# NewBoard.net
KiCad netlist of a schematic drawn in EAGLE
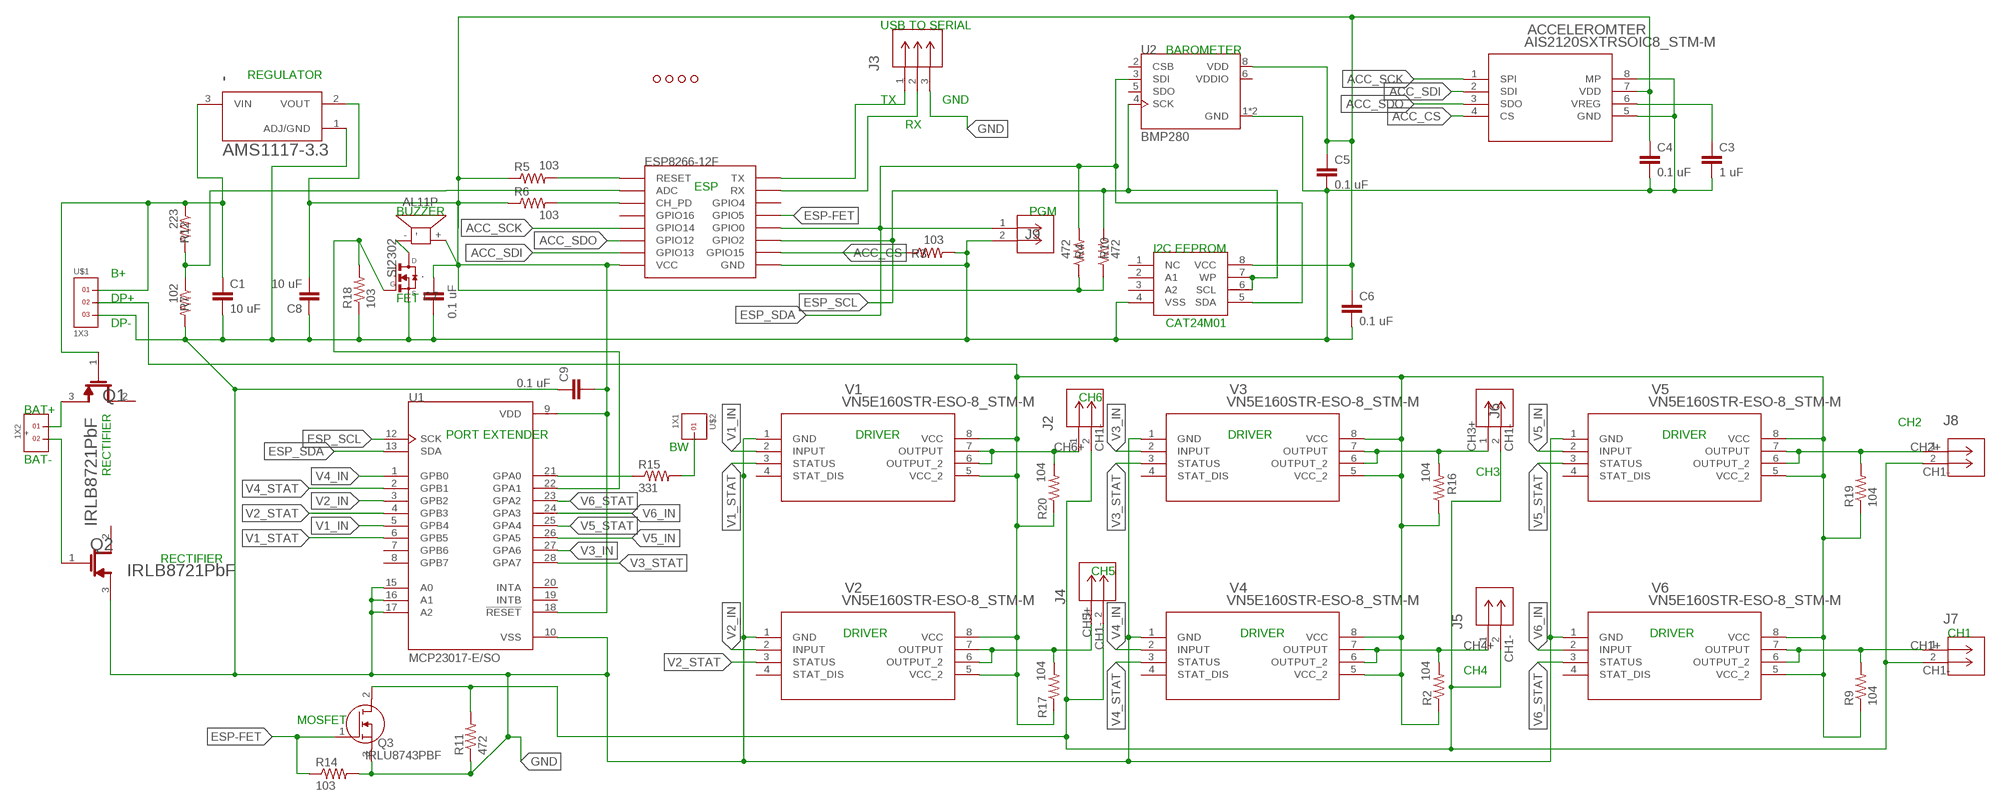
[diagram p0: schematic, sheet 1]

(export (version "E")
  (design (tool "Eeschema 10.0.6"))
  (components
    (comp (ref "'")
      (value "AMS1117-3.3")
      (footprint "eagle-import:SOT229P700X180-4N")
      (fields (field (name "MF") "Advanced Monolithic Systems"))
      (libsource (lib "eagle-import") (part "AMS1117-3.3"))
    )
    (comp (ref "+")
      (value "1X2")
      (footprint "eagle-import:1X2")
      (libsource (lib "eagle-import") (part "1X2"))
    )
    (comp (ref ",")
      (value "AL11P")
      (footprint "eagle-import:AL11P")
      (libsource (lib "eagle-import") (part "AL11P"))
    )
    (comp (ref ".")
      (value "SI2302")
      (footprint "eagle-import:SOT23")
      (fields (field (name "MF") "Vishay Siliconix"))
      (libsource (lib "eagle-import") (part "SI2302"))
    )
    (comp (ref "ACCELEROMTER")
      (value "AIS2120SXTRSOIC8_STM-M")
      (footprint "eagle-import:SOIC8_STM-M")
      (fields
        (field (name "MANUFACTURER_PART_NUMBER") "AIS2120SXTR")
        (field (name "COPYRIGHT") "Copyright (C) 2022 Ultra Librarian. All rights reserved.")
      )
      (libsource (lib "eagle-import") (part "AIS2120SXTRSOIC8_STM-M"))
    )
    (comp (ref "C1")
      (value "10 uF")
      (footprint "eagle-import:C1206")
      (libsource (lib "eagle-import") (part "C-EUC1206"))
    )
    (comp (ref "C3")
      (value "1 uF")
      (footprint "eagle-import:C1206")
      (libsource (lib "eagle-import") (part "C-EUC1206"))
    )
    (comp (ref "C4")
      (value "0.1 uF")
      (footprint "eagle-import:C1206")
      (libsource (lib "eagle-import") (part "C-EUC1206"))
    )
    (comp (ref "C5")
      (value "0.1 uF")
      (footprint "eagle-import:C1206")
      (libsource (lib "eagle-import") (part "C-EUC1206"))
    )
    (comp (ref "C6")
      (value "0.1 uF")
      (footprint "eagle-import:C1206")
      (libsource (lib "eagle-import") (part "C-EUC1206"))
    )
    (comp (ref "C7")
      (value "0.1 uF")
      (footprint "eagle-import:C1206")
      (libsource (lib "eagle-import") (part "C-EUC1206"))
    )
    (comp (ref "C8")
      (value "10 uF")
      (footprint "eagle-import:C1206")
      (libsource (lib "eagle-import") (part "C-EUC1206"))
    )
    (comp (ref "C9")
      (value "0.1 uF")
      (footprint "eagle-import:C1206")
      (libsource (lib "eagle-import") (part "C-EUC1206"))
    )
    (comp (ref "CAT24M01A_EEPROM")
      (value "CAT24M01WI-GT3")
      (footprint "eagle-import:SO08")
      (fields (field (name "MF") "onsemi"))
      (libsource (lib "eagle-import") (part "CAT24M01WI-GT3"))
    )
    (comp (ref "ESP8266-12F")
      (value "ESP12SMD")
      (footprint "eagle-import:ESP12-SMD")
      (libsource (lib "eagle-import") (part "ESP12SMD"))
    )
    (comp (ref "J2")
      (value "61300211121")
      (footprint "eagle-import:CONN_61300211121_WRE")
      (fields (field (name "COPYRIGHT") "Copyright (C) 2022 Ultra Librarian. All rights reserved."))
      (libsource (lib "eagle-import") (part "61300211121"))
    )
    (comp (ref "J3")
      (value "68000-103HLF")
      (footprint "eagle-import:CONN_68000-103HLF_AMP")
      (fields (field (name "COPYRIGHT") "Copyright (C) 2022 Ultra Librarian. All rights reserved."))
      (libsource (lib "eagle-import") (part "68000-103HLF"))
    )
    (comp (ref "J4")
      (value "61300211121")
      (footprint "eagle-import:CONN_61300211121_WRE")
      (fields (field (name "COPYRIGHT") "Copyright (C) 2022 Ultra Librarian. All rights reserved."))
      (libsource (lib "eagle-import") (part "61300211121"))
    )
    (comp (ref "J5")
      (value "61300211121")
      (footprint "eagle-import:CONN_61300211121_WRE")
      (fields (field (name "COPYRIGHT") "Copyright (C) 2022 Ultra Librarian. All rights reserved."))
      (libsource (lib "eagle-import") (part "61300211121"))
    )
    (comp (ref "J6")
      (value "61300211121")
      (footprint "eagle-import:CONN_61300211121_WRE")
      (fields (field (name "COPYRIGHT") "Copyright (C) 2022 Ultra Librarian. All rights reserved."))
      (libsource (lib "eagle-import") (part "61300211121"))
    )
    (comp (ref "J7")
      (value "61300211121")
      (footprint "eagle-import:CONN_61300211121_WRE")
      (fields (field (name "COPYRIGHT") "Copyright (C) 2022 Ultra Librarian. All rights reserved."))
      (libsource (lib "eagle-import") (part "61300211121"))
    )
    (comp (ref "J8")
      (value "61300211121")
      (footprint "eagle-import:CONN_61300211121_WRE")
      (fields (field (name "COPYRIGHT") "Copyright (C) 2022 Ultra Librarian. All rights reserved."))
      (libsource (lib "eagle-import") (part "61300211121"))
    )
    (comp (ref "J9")
      (value "61300211121")
      (footprint "eagle-import:CONN_61300211121_WRE")
      (fields (field (name "COPYRIGHT") "Copyright (C) 2022 Ultra Librarian. All rights reserved."))
      (libsource (lib "eagle-import") (part "61300211121"))
    )
    (comp (ref "Q1")
      (value "INFINEON_IRLB8721PBFINFINEON_IRLB8721PBF_0_0")
      (footprint "eagle-import:INFINEON_IRLB8721PBF_0")
      (fields
        (field (name "DIGIKEY_PART_NUMBER") "IRLB8721PBF-ND")
        (field (name "MF") "Infineon")
        (field (name "MOUSER_PART_NUMBER") "942-IRLB8721PBF")
      )
      (libsource (lib "eagle-import") (part "INFINEON_IRLB8721PBFINFINEON_IRLB8721PBF_0_0"))
    )
    (comp (ref "Q2")
      (value "INFINEON_IRLB8721PBFINFINEON_IRLB8721PBF_0_0")
      (footprint "eagle-import:INFINEON_IRLB8721PBF_0")
      (fields
        (field (name "DIGIKEY_PART_NUMBER") "IRLB8721PBF-ND")
        (field (name "MF") "Infineon")
        (field (name "MOUSER_PART_NUMBER") "942-IRLB8721PBF")
      )
      (libsource (lib "eagle-import") (part "INFINEON_IRLB8721PBFINFINEON_IRLB8721PBF_0_0"))
    )
    (comp (ref "Q3")
      (value "IRLU8743PBF")
      (footprint "eagle-import:TO229P239X654X978-3P")
      (fields (field (name "MOUSER_PART_NUMBER") "942-IRLU8743PBF"))
      (libsource (lib "eagle-import") (part "IRLU8743PBF"))
    )
    (comp (ref "R2")
      (value "104")
      (footprint "eagle-import:R2010")
      (libsource (lib "eagle-import") (part "R-US_R2010"))
    )
    (comp (ref "R3")
      (value "103")
      (footprint "eagle-import:R2010")
      (libsource (lib "eagle-import") (part "R-US_R2010"))
    )
    (comp (ref "R4")
      (value "472")
      (footprint "eagle-import:R2010")
      (libsource (lib "eagle-import") (part "R-US_R2010"))
    )
    (comp (ref "R5")
      (value "103")
      (footprint "eagle-import:R2010")
      (libsource (lib "eagle-import") (part "R-US_R2010"))
    )
    (comp (ref "R6")
      (value "103")
      (footprint "eagle-import:R2010")
      (libsource (lib "eagle-import") (part "R-US_R2010"))
    )
    (comp (ref "R7")
      (value "102")
      (footprint "eagle-import:R2010")
      (libsource (lib "eagle-import") (part "R-US_R2010"))
    )
    (comp (ref "R9")
      (value "104")
      (footprint "eagle-import:R2010")
      (libsource (lib "eagle-import") (part "R-US_R2010"))
    )
    (comp (ref "R10")
      (value "472")
      (footprint "eagle-import:R2010")
      (libsource (lib "eagle-import") (part "R-US_R2010"))
    )
    (comp (ref "R11")
      (value "472")
      (footprint "eagle-import:R2010")
      (libsource (lib "eagle-import") (part "R-US_R2010"))
    )
    (comp (ref "R12")
      (value "223")
      (footprint "eagle-import:R2010")
      (libsource (lib "eagle-import") (part "R-US_R2010"))
    )
    (comp (ref "R14")
      (value "103")
      (footprint "eagle-import:R2010")
      (libsource (lib "eagle-import") (part "R-US_R2010"))
    )
    (comp (ref "R15")
      (value "331")
      (footprint "eagle-import:R2010")
      (libsource (lib "eagle-import") (part "R-US_R2010"))
    )
    (comp (ref "R16")
      (value "104")
      (footprint "eagle-import:R2010")
      (libsource (lib "eagle-import") (part "R-US_R2010"))
    )
    (comp (ref "R17")
      (value "104")
      (footprint "eagle-import:R2010")
      (libsource (lib "eagle-import") (part "R-US_R2010"))
    )
    (comp (ref "R18")
      (value "103")
      (footprint "eagle-import:R2010")
      (libsource (lib "eagle-import") (part "R-US_R2010"))
    )
    (comp (ref "R19")
      (value "104")
      (footprint "eagle-import:R2010")
      (libsource (lib "eagle-import") (part "R-US_R2010"))
    )
    (comp (ref "R20")
      (value "104")
      (footprint "eagle-import:R2010")
      (libsource (lib "eagle-import") (part "R-US_R2010"))
    )
    (comp (ref "U$1")
      (value "1X3")
      (footprint "eagle-import:1X3")
      (libsource (lib "eagle-import") (part "1X3"))
    )
    (comp (ref "U$2")
      (value "1X1")
      (footprint "eagle-import:1X1")
      (libsource (lib "eagle-import") (part "1X1"))
    )
    (comp (ref "U$3")
      (value "HOLE.4MM")
      (footprint "eagle-import:#4")
      (libsource (lib "eagle-import") (part "HOLE.4MM"))
    )
    (comp (ref "U$4")
      (value "HOLE.4MM")
      (footprint "eagle-import:#4")
      (libsource (lib "eagle-import") (part "HOLE.4MM"))
    )
    (comp (ref "U$5")
      (value "HOLE.4MM")
      (footprint "eagle-import:#4")
      (libsource (lib "eagle-import") (part "HOLE.4MM"))
    )
    (comp (ref "U$6")
      (value "HOLE.4MM")
      (footprint "eagle-import:#4")
      (libsource (lib "eagle-import") (part "HOLE.4MM"))
    )
    (comp (ref "U1")
      (value "MCP23017-E/SO")
      (footprint "eagle-import:SOIC127P1030X265-28N")
      (fields (field (name "MF") "Microchip"))
      (libsource (lib "eagle-import") (part "MCP23017-E/SO"))
    )
    (comp (ref "U2")
      (value "BMP280")
      (footprint "eagle-import:XDCR_BMP280")
      (fields (field (name "MF") "Bosch"))
      (libsource (lib "eagle-import") (part "BMP280"))
    )
    (comp (ref "V1")
      (value "VN5E160STR-ESO-8_STM-M")
      (footprint "eagle-import:SO-8_STM-M")
      (fields
        (field (name "MANUFACTURER_PART_NUMBER") "VN5E160STR-E")
        (field (name "COPYRIGHT") "Copyright (C) 2022 Ultra Librarian. All rights reserved.")
      )
      (libsource (lib "eagle-import") (part "VN5E160STR-ESO-8_STM-M"))
    )
    (comp (ref "V2")
      (value "VN5E160STR-ESO-8_STM-M")
      (footprint "eagle-import:SO-8_STM-M")
      (fields
        (field (name "MANUFACTURER_PART_NUMBER") "VN5E160STR-E")
        (field (name "COPYRIGHT") "Copyright (C) 2022 Ultra Librarian. All rights reserved.")
      )
      (libsource (lib "eagle-import") (part "VN5E160STR-ESO-8_STM-M"))
    )
    (comp (ref "V3")
      (value "VN5E160STR-ESO-8_STM-M")
      (footprint "eagle-import:SO-8_STM-M")
      (fields
        (field (name "MANUFACTURER_PART_NUMBER") "VN5E160STR-E")
        (field (name "COPYRIGHT") "Copyright (C) 2022 Ultra Librarian. All rights reserved.")
      )
      (libsource (lib "eagle-import") (part "VN5E160STR-ESO-8_STM-M"))
    )
    (comp (ref "V4")
      (value "VN5E160STR-ESO-8_STM-M")
      (footprint "eagle-import:SO-8_STM-M")
      (fields
        (field (name "MANUFACTURER_PART_NUMBER") "VN5E160STR-E")
        (field (name "COPYRIGHT") "Copyright (C) 2022 Ultra Librarian. All rights reserved.")
      )
      (libsource (lib "eagle-import") (part "VN5E160STR-ESO-8_STM-M"))
    )
    (comp (ref "V5")
      (value "VN5E160STR-ESO-8_STM-M")
      (footprint "eagle-import:SO-8_STM-M")
      (fields
        (field (name "MANUFACTURER_PART_NUMBER") "VN5E160STR-E")
        (field (name "COPYRIGHT") "Copyright (C) 2022 Ultra Librarian. All rights reserved.")
      )
      (libsource (lib "eagle-import") (part "VN5E160STR-ESO-8_STM-M"))
    )
    (comp (ref "V6")
      (value "VN5E160STR-ESO-8_STM-M")
      (footprint "eagle-import:SO-8_STM-M")
      (fields
        (field (name "MANUFACTURER_PART_NUMBER") "VN5E160STR-E")
        (field (name "COPYRIGHT") "Copyright (C) 2022 Ultra Librarian. All rights reserved.")
      )
      (libsource (lib "eagle-import") (part "VN5E160STR-ESO-8_STM-M"))
    )
  )
  (nets
    (net (code "1") (name "/CH1+") (class "Default")
      (node (ref "J7") (pin "1") (pinfunction "1_1") (pintype "passive"))
      (node (ref "R9") (pin "2") (pinfunction "2_2") (pintype "passive"))
      (node (ref "V6") (pin "6") (pinfunction "OUTPUT_2_6") (pintype "output"))
      (node (ref "V6") (pin "7") (pinfunction "OUTPUT_7") (pintype "output"))
    )
    (net (code "2") (name "/CH1-") (class "Default")
      (node (ref "J2") (pin "2") (pinfunction "2_2") (pintype "passive"))
      (node (ref "J4") (pin "2") (pinfunction "2_2") (pintype "passive"))
      (node (ref "J5") (pin "2") (pinfunction "2_2") (pintype "passive"))
      (node (ref "J6") (pin "2") (pinfunction "2_2") (pintype "passive"))
      (node (ref "J7") (pin "2") (pinfunction "2_2") (pintype "passive"))
      (node (ref "J8") (pin "2") (pinfunction "2_2") (pintype "passive"))
      (node (ref "Q3") (pin "2") (pinfunction "D_2") (pintype "bidirectional"))
      (node (ref "R11") (pin "2") (pinfunction "2_2") (pintype "passive"))
    )
    (net (code "3") (name "/CH2+") (class "Default")
      (node (ref "J8") (pin "1") (pinfunction "1_1") (pintype "passive"))
      (node (ref "R19") (pin "2") (pinfunction "2_2") (pintype "passive"))
      (node (ref "V5") (pin "6") (pinfunction "OUTPUT_2_6") (pintype "output"))
      (node (ref "V5") (pin "7") (pinfunction "OUTPUT_7") (pintype "output"))
    )
    (net (code "4") (name "/CH3+") (class "Default")
      (node (ref "J6") (pin "1") (pinfunction "1_1") (pintype "passive"))
      (node (ref "R16") (pin "2") (pinfunction "2_2") (pintype "passive"))
      (node (ref "V3") (pin "6") (pinfunction "OUTPUT_2_6") (pintype "output"))
      (node (ref "V3") (pin "7") (pinfunction "OUTPUT_7") (pintype "output"))
    )
    (net (code "5") (name "/CH4+") (class "Default")
      (node (ref "J5") (pin "1") (pinfunction "1_1") (pintype "passive"))
      (node (ref "R2") (pin "2") (pinfunction "2_2") (pintype "passive"))
      (node (ref "V4") (pin "6") (pinfunction "OUTPUT_2_6") (pintype "output"))
      (node (ref "V4") (pin "7") (pinfunction "OUTPUT_7") (pintype "output"))
    )
    (net (code "6") (name "/CH5+") (class "Default")
      (node (ref "J4") (pin "1") (pinfunction "1_1") (pintype "passive"))
      (node (ref "R17") (pin "2") (pinfunction "2_2") (pintype "passive"))
      (node (ref "V2") (pin "6") (pinfunction "OUTPUT_2_6") (pintype "output"))
      (node (ref "V2") (pin "7") (pinfunction "OUTPUT_7") (pintype "output"))
    )
    (net (code "7") (name "/CH6+") (class "Default")
      (node (ref "J2") (pin "1") (pinfunction "1_1") (pintype "passive"))
      (node (ref "R20") (pin "2") (pinfunction "2_2") (pintype "passive"))
      (node (ref "V1") (pin "6") (pinfunction "OUTPUT_2_6") (pintype "output"))
      (node (ref "V1") (pin "7") (pinfunction "OUTPUT_7") (pintype "output"))
    )
    (net (code "8") (name "/VDDIO") (class "Default")
      (node (ref "U2") (pin "6") (pinfunction "VDDIO_6") (pintype "power_in"))
    )
    (net (code "9") (name "ACC_CS") (class "Default")
      (node (ref "ACCELEROMTER") (pin "4") (pinfunction "CS_4") (pintype "input"))
      (node (ref "ESP8266-12F") (pin "GPIO15") (pinfunction "GPIO15_GPIO15") (pintype "bidirectional"))
      (node (ref "R3") (pin "1") (pinfunction "1_1") (pintype "passive"))
    )
    (net (code "10") (name "ACC_SCK") (class "Default")
      (node (ref "ACCELEROMTER") (pin "1") (pinfunction "SPI_1") (pintype "input"))
      (node (ref "ESP8266-12F") (pin "GPIO14") (pinfunction "GPIO14_GPIO14") (pintype "bidirectional"))
    )
    (net (code "11") (name "ACC_SDI") (class "Default")
      (node (ref "ACCELEROMTER") (pin "2") (pinfunction "SDI_2") (pintype "input"))
      (node (ref "ESP8266-12F") (pin "GPIO13") (pinfunction "GPIO13_GPIO13") (pintype "bidirectional"))
    )
    (net (code "12") (name "ACC_SDO") (class "Default")
      (node (ref "ACCELEROMTER") (pin "3") (pinfunction "SDO_3") (pintype "output"))
      (node (ref "ESP8266-12F") (pin "GPIO12") (pinfunction "GPIO12_GPIO12") (pintype "bidirectional"))
    )
    (net (code "13") (name "ESP-FET") (class "Default")
      (node (ref "ESP8266-12F") (pin "GPIO5") (pinfunction "GPIO5_GPIO5") (pintype "bidirectional"))
      (node (ref "Q3") (pin "1") (pinfunction "G_1") (pintype "bidirectional"))
      (node (ref "R14") (pin "1") (pinfunction "1_1") (pintype "passive"))
    )
    (net (code "14") (name "ESP_SCL") (class "Default")
      (node (ref "CAT24M01A_EEPROM") (pin "6") (pinfunction "SCL_6") (pintype "bidirectional"))
      (node (ref "CAT24M01A_EEPROM") (pin "7") (pinfunction "WP_7") (pintype "bidirectional"))
      (node (ref "ESP8266-12F") (pin "GPIO2") (pinfunction "GPIO2_GPIO2") (pintype "bidirectional"))
      (node (ref "R10") (pin "2") (pinfunction "2_2") (pintype "passive"))
      (node (ref "U1") (pin "12") (pinfunction "SCK_12") (pintype "input"))
      (node (ref "U2") (pin "4") (pinfunction "SCK_4") (pintype "input"))
    )
    (net (code "15") (name "ESP_SDA") (class "Default")
      (node (ref "CAT24M01A_EEPROM") (pin "5") (pinfunction "SDA_5") (pintype "bidirectional"))
      (node (ref "ESP8266-12F") (pin "GPIO0") (pinfunction "GPIO0_GPIO0") (pintype "bidirectional"))
      (node (ref "J9") (pin "1") (pinfunction "1_1") (pintype "passive"))
      (node (ref "R4") (pin "2") (pinfunction "2_2") (pintype "passive"))
      (node (ref "U1") (pin "13") (pinfunction "SDA_13") (pintype "bidirectional"))
      (node (ref "U2") (pin "3") (pinfunction "SDI_3") (pintype "bidirectional"))
    )
    (net (code "16") (name "GND") (class "Default")
      (node (ref "'") (pin "1") (pinfunction "ADJ/GND_1") (pintype "power_in"))
      (node (ref ".") (pin "2") (pinfunction "S_2") (pintype "passive"))
      (node (ref "ACCELEROMTER") (pin "5") (pinfunction "GND_5") (pintype "passive"))
      (node (ref "ACCELEROMTER") (pin "8") (pinfunction "MP_8") (pintype "passive"))
      (node (ref "C1") (pin "2") (pinfunction "2_2") (pintype "passive"))
      (node (ref "C3") (pin "2") (pinfunction "2_2") (pintype "passive"))
      (node (ref "C4") (pin "2") (pinfunction "2_2") (pintype "passive"))
      (node (ref "C5") (pin "2") (pinfunction "2_2") (pintype "passive"))
      (node (ref "C6") (pin "2") (pinfunction "2_2") (pintype "passive"))
      (node (ref "C7") (pin "1") (pinfunction "1_1") (pintype "passive"))
      (node (ref "C8") (pin "1") (pinfunction "1_1") (pintype "passive"))
      (node (ref "C9") (pin "1") (pinfunction "1_1") (pintype "passive"))
      (node (ref "CAT24M01A_EEPROM") (pin "4") (pinfunction "VSS_4") (pintype "bidirectional"))
      (node (ref "ESP8266-12F") (pin "GND") (pinfunction "GND_GND") (pintype "bidirectional"))
      (node (ref "J3") (pin "3") (pinfunction "3_3") (pintype "passive"))
      (node (ref "J9") (pin "2") (pinfunction "2_2") (pintype "passive"))
      (node (ref "Q2") (pin "3") (pinfunction "S_3") (pintype "bidirectional"))
      (node (ref "Q3") (pin "3") (pinfunction "S_3") (pintype "bidirectional"))
      (node (ref "R11") (pin "1") (pinfunction "1_1") (pintype "passive"))
      (node (ref "R14") (pin "2") (pinfunction "2_2") (pintype "passive"))
      (node (ref "R18") (pin "1") (pinfunction "1_1") (pintype "passive"))
      (node (ref "R3") (pin "2") (pinfunction "2_2") (pintype "passive"))
      (node (ref "R7") (pin "2") (pinfunction "2_2") (pintype "passive"))
      (node (ref "U$1") (pin "3") (pinfunction "3_3") (pintype "bidirectional"))
      (node (ref "U1") (pin "10") (pinfunction "VSS_10") (pintype "power_in"))
      (node (ref "U1") (pin "15") (pinfunction "A0_15") (pintype "input"))
      (node (ref "U1") (pin "16") (pinfunction "A1_16") (pintype "input"))
      (node (ref "U1") (pin "17") (pinfunction "A2_17") (pintype "input"))
      (node (ref "U2") (pin "1") (pinfunction "GND_1") (pintype "power_in"))
      (node (ref "U2") (pin "7") (pinfunction "GND_7") (pintype "power_in"))
      (node (ref "V1") (pin "1") (pinfunction "GND_1") (pintype "power_in"))
      (node (ref "V2") (pin "1") (pinfunction "GND_1") (pintype "power_in"))
      (node (ref "V3") (pin "1") (pinfunction "GND_1") (pintype "power_in"))
      (node (ref "V4") (pin "1") (pinfunction "GND_1") (pintype "power_in"))
      (node (ref "V5") (pin "1") (pinfunction "GND_1") (pintype "power_in"))
      (node (ref "V6") (pin "1") (pinfunction "GND_1") (pintype "power_in"))
    )
    (net (code "17") (name "Net-('-VIN)") (class "Default")
      (node (ref "'") (pin "3") (pinfunction "VIN_3") (pintype "input"))
      (node (ref "C1") (pin "1") (pinfunction "1_1") (pintype "passive"))
      (node (ref "Q1") (pin "1") (pinfunction "G_1") (pintype "bidirectional"))
      (node (ref "R12") (pin "1") (pinfunction "1_1") (pintype "passive"))
      (node (ref "U$1") (pin "1") (pinfunction "1_1") (pintype "bidirectional"))
    )
    (net (code "18") (name "Net-('-VOUT)") (class "Default")
      (node (ref "'") (pin "2") (pinfunction "VOUT_2") (pintype "output"))
      (node (ref ",") (pin "+") (pinfunction "2_+") (pintype "passive"))
      (node (ref "ACCELEROMTER") (pin "7") (pinfunction "VDD_7") (pintype "power_in"))
      (node (ref "C4") (pin "1") (pinfunction "1_1") (pintype "passive"))
      (node (ref "C5") (pin "1") (pinfunction "1_1") (pintype "passive"))
      (node (ref "C6") (pin "1") (pinfunction "1_1") (pintype "passive"))
      (node (ref "C7") (pin "2") (pinfunction "2_2") (pintype "passive"))
      (node (ref "C8") (pin "2") (pinfunction "2_2") (pintype "passive"))
      (node (ref "C9") (pin "2") (pinfunction "2_2") (pintype "passive"))
      (node (ref "CAT24M01A_EEPROM") (pin "8") (pinfunction "VCC_8") (pintype "bidirectional"))
      (node (ref "ESP8266-12F") (pin "VCC") (pinfunction "VCC_VCC") (pintype "bidirectional"))
      (node (ref "R10") (pin "1") (pinfunction "1_1") (pintype "passive"))
      (node (ref "R4") (pin "1") (pinfunction "1_1") (pintype "passive"))
      (node (ref "R5") (pin "1") (pinfunction "1_1") (pintype "passive"))
      (node (ref "R6") (pin "1") (pinfunction "1_1") (pintype "passive"))
      (node (ref "U1") (pin "18") (pinfunction "~{RESET}_18") (pintype "output"))
      (node (ref "U1") (pin "9") (pinfunction "VDD_9") (pintype "power_in"))
      (node (ref "U2") (pin "8") (pinfunction "VDD_8") (pintype "power_in"))
    )
    (net (code "19") (name "Net-(,-1)") (class "Default")
      (node (ref ",") (pin "-") (pinfunction "1_-") (pintype "passive"))
      (node (ref ".") (pin "3") (pinfunction "D_3") (pintype "passive"))
    )
    (net (code "20") (name "Net-(.-G)") (class "Default")
      (node (ref ".") (pin "1") (pinfunction "G_1") (pintype "passive"))
      (node (ref "R18") (pin "2") (pinfunction "2_2") (pintype "passive"))
      (node (ref "U1") (pin "22") (pinfunction "GPA1_22") (pintype "bidirectional"))
    )
    (net (code "21") (name "Net-(ACCELEROMTER-VREG)") (class "Default")
      (node (ref "ACCELEROMTER") (pin "6") (pinfunction "VREG_6") (pintype "power_in"))
      (node (ref "C3") (pin "1") (pinfunction "1_1") (pintype "passive"))
    )
    (net (code "22") (name "Net-(ESP8266-12F-PadADC)") (class "Default")
      (node (ref "ESP8266-12F") (pin "ADC") (pinfunction "ADC_ADC") (pintype "bidirectional"))
      (node (ref "R12") (pin "2") (pinfunction "2_2") (pintype "passive"))
      (node (ref "R7") (pin "1") (pinfunction "1_1") (pintype "passive"))
    )
    (net (code "23") (name "Net-(ESP8266-12F-PadCH_PD)") (class "Default")
      (node (ref "ESP8266-12F") (pin "CH_PD") (pinfunction "CH_PD_CH_PD") (pintype "bidirectional"))
      (node (ref "R6") (pin "2") (pinfunction "2_2") (pintype "passive"))
    )
    (net (code "24") (name "Net-(ESP8266-12F-PadRESET)") (class "Default")
      (node (ref "ESP8266-12F") (pin "RESET") (pinfunction "RESET_RESET") (pintype "bidirectional"))
      (node (ref "R5") (pin "2") (pinfunction "2_2") (pintype "passive"))
    )
    (net (code "25") (name "Net-(ESP8266-12F-RX)") (class "Default")
      (node (ref "ESP8266-12F") (pin "RXD0") (pinfunction "RX_RXD0") (pintype "bidirectional"))
      (node (ref "J3") (pin "2") (pinfunction "2_2") (pintype "passive"))
    )
    (net (code "26") (name "Net-(ESP8266-12F-TX)") (class "Default")
      (node (ref "ESP8266-12F") (pin "TXD0") (pinfunction "TX_TXD0") (pintype "bidirectional"))
      (node (ref "J3") (pin "1") (pinfunction "1_1") (pintype "passive"))
    )
    (net (code "27") (name "Net-(Q1-S)") (class "Default")
      (node (ref "+") (pin "1") (pinfunction "1_1") (pintype "bidirectional"))
      (node (ref "Q1") (pin "3") (pinfunction "S_3") (pintype "bidirectional"))
    )
    (net (code "28") (name "Net-(Q2-G)") (class "Default")
      (node (ref "+") (pin "2") (pinfunction "2_2") (pintype "bidirectional"))
      (node (ref "Q2") (pin "1") (pinfunction "G_1") (pintype "bidirectional"))
    )
    (net (code "29") (name "Net-(R15-Pad2)") (class "Default")
      (node (ref "R15") (pin "2") (pinfunction "2_2") (pintype "passive"))
      (node (ref "U$2") (pin "1") (pinfunction "1_1") (pintype "bidirectional"))
    )
    (net (code "30") (name "Net-(U1-GPA0)") (class "Default")
      (node (ref "R15") (pin "1") (pinfunction "1_1") (pintype "passive"))
      (node (ref "U1") (pin "21") (pinfunction "GPA0_21") (pintype "bidirectional"))
    )
    (net (code "31") (name "Net-(V1-VCC)") (class "Default")
      (node (ref "R16") (pin "1") (pinfunction "1_1") (pintype "passive"))
      (node (ref "R17") (pin "1") (pinfunction "1_1") (pintype "passive"))
      (node (ref "R19") (pin "1") (pinfunction "1_1") (pintype "passive"))
      (node (ref "R2") (pin "1") (pinfunction "1_1") (pintype "passive"))
      (node (ref "R20") (pin "1") (pinfunction "1_1") (pintype "passive"))
      (node (ref "R9") (pin "1") (pinfunction "1_1") (pintype "passive"))
      (node (ref "U$1") (pin "2") (pinfunction "2_2") (pintype "bidirectional"))
      (node (ref "V1") (pin "5") (pinfunction "VCC_2_5") (pintype "power_in"))
      (node (ref "V1") (pin "8") (pinfunction "VCC_8") (pintype "power_in"))
      (node (ref "V2") (pin "5") (pinfunction "VCC_2_5") (pintype "power_in"))
      (node (ref "V2") (pin "8") (pinfunction "VCC_8") (pintype "power_in"))
      (node (ref "V3") (pin "5") (pinfunction "VCC_2_5") (pintype "power_in"))
      (node (ref "V3") (pin "8") (pinfunction "VCC_8") (pintype "power_in"))
      (node (ref "V4") (pin "5") (pinfunction "VCC_2_5") (pintype "power_in"))
      (node (ref "V4") (pin "8") (pinfunction "VCC_8") (pintype "power_in"))
      (node (ref "V5") (pin "5") (pinfunction "VCC_2_5") (pintype "power_in"))
      (node (ref "V5") (pin "8") (pinfunction "VCC_8") (pintype "power_in"))
      (node (ref "V6") (pin "5") (pinfunction "VCC_2_5") (pintype "power_in"))
      (node (ref "V6") (pin "8") (pinfunction "VCC_8") (pintype "power_in"))
    )
    (net (code "32") (name "V1_IN") (class "Default")
      (node (ref "U1") (pin "5") (pinfunction "GPB4_5") (pintype "bidirectional"))
      (node (ref "V1") (pin "2") (pinfunction "INPUT_2") (pintype "input"))
    )
    (net (code "33") (name "V1_STAT") (class "Default")
      (node (ref "U1") (pin "6") (pinfunction "GPB5_6") (pintype "bidirectional"))
      (node (ref "V1") (pin "3") (pinfunction "STATUS_3") (pintype "passive"))
    )
    (net (code "34") (name "V2_IN") (class "Default")
      (node (ref "U1") (pin "3") (pinfunction "GPB2_3") (pintype "bidirectional"))
      (node (ref "V2") (pin "2") (pinfunction "INPUT_2") (pintype "input"))
    )
    (net (code "35") (name "V2_STAT") (class "Default")
      (node (ref "U1") (pin "4") (pinfunction "GPB3_4") (pintype "bidirectional"))
      (node (ref "V2") (pin "3") (pinfunction "STATUS_3") (pintype "passive"))
    )
    (net (code "36") (name "V3_IN") (class "Default")
      (node (ref "U1") (pin "27") (pinfunction "GPA6_27") (pintype "bidirectional"))
      (node (ref "V3") (pin "2") (pinfunction "INPUT_2") (pintype "input"))
    )
    (net (code "37") (name "V3_STAT") (class "Default")
      (node (ref "U1") (pin "28") (pinfunction "GPA7_28") (pintype "bidirectional"))
      (node (ref "V3") (pin "3") (pinfunction "STATUS_3") (pintype "passive"))
    )
    (net (code "38") (name "V4_IN") (class "Default")
      (node (ref "U1") (pin "1") (pinfunction "GPB0_1") (pintype "bidirectional"))
      (node (ref "V4") (pin "2") (pinfunction "INPUT_2") (pintype "input"))
    )
    (net (code "39") (name "V4_STAT") (class "Default")
      (node (ref "U1") (pin "2") (pinfunction "GPB1_2") (pintype "bidirectional"))
      (node (ref "V4") (pin "3") (pinfunction "STATUS_3") (pintype "passive"))
    )
    (net (code "40") (name "V5_IN") (class "Default")
      (node (ref "U1") (pin "26") (pinfunction "GPA5_26") (pintype "bidirectional"))
      (node (ref "V5") (pin "2") (pinfunction "INPUT_2") (pintype "input"))
    )
    (net (code "41") (name "V5_STAT") (class "Default")
      (node (ref "U1") (pin "25") (pinfunction "GPA4_25") (pintype "bidirectional"))
      (node (ref "V5") (pin "3") (pinfunction "STATUS_3") (pintype "passive"))
    )
    (net (code "42") (name "V6_IN") (class "Default")
      (node (ref "U1") (pin "24") (pinfunction "GPA3_24") (pintype "bidirectional"))
      (node (ref "V6") (pin "2") (pinfunction "INPUT_2") (pintype "input"))
    )
    (net (code "43") (name "V6_STAT") (class "Default")
      (node (ref "U1") (pin "23") (pinfunction "GPA2_23") (pintype "bidirectional"))
      (node (ref "V6") (pin "3") (pinfunction "STATUS_3") (pintype "passive"))
    )
    (net (code "44") (name "unconnected-(CAT24M01A_EEPROM-A1-Pad2)") (class "Default")
      (node (ref "CAT24M01A_EEPROM") (pin "2") (pinfunction "A1_2") (pintype "bidirectional"))
    )
    (net (code "45") (name "unconnected-(CAT24M01A_EEPROM-A2-Pad3)") (class "Default")
      (node (ref "CAT24M01A_EEPROM") (pin "3") (pinfunction "A2_3") (pintype "bidirectional"))
    )
    (net (code "46") (name "unconnected-(CAT24M01A_EEPROM-NC-Pad1)") (class "Default")
      (node (ref "CAT24M01A_EEPROM") (pin "1") (pinfunction "NC_1") (pintype "bidirectional"))
    )
    (net (code "47") (name "unconnected-(ESP8266-12F-PadGPIO4)") (class "Default")
      (node (ref "ESP8266-12F") (pin "GPIO4") (pinfunction "GPIO4_GPIO4") (pintype "bidirectional"))
    )
    (net (code "48") (name "unconnected-(ESP8266-12F-PadGPIO16)") (class "Default")
      (node (ref "ESP8266-12F") (pin "GPIO16") (pinfunction "GPIO16_GPIO16") (pintype "bidirectional"))
    )
    (net (code "49") (name "unconnected-(Q1-D-Pad2)") (class "Default")
      (node (ref "Q1") (pin "2") (pinfunction "D_2") (pintype "bidirectional"))
    )
    (net (code "50") (name "unconnected-(Q2-D-Pad2)") (class "Default")
      (node (ref "Q2") (pin "2") (pinfunction "D_2") (pintype "bidirectional"))
    )
    (net (code "51") (name "unconnected-(U1-GPB6-Pad7)") (class "Default")
      (node (ref "U1") (pin "7") (pinfunction "GPB6_7") (pintype "bidirectional"))
    )
    (net (code "52") (name "unconnected-(U1-GPB7-Pad8)") (class "Default")
      (node (ref "U1") (pin "8") (pinfunction "GPB7_8") (pintype "bidirectional"))
    )
    (net (code "53") (name "unconnected-(U1-INTA-Pad20)") (class "Default")
      (node (ref "U1") (pin "20") (pinfunction "INTA_20") (pintype "output"))
    )
    (net (code "54") (name "unconnected-(U1-INTB-Pad19)") (class "Default")
      (node (ref "U1") (pin "19") (pinfunction "INTB_19") (pintype "output"))
    )
    (net (code "55") (name "unconnected-(U2-CSB-Pad2)") (class "Default")
      (node (ref "U2") (pin "2") (pinfunction "CSB_2") (pintype "input"))
    )
    (net (code "56") (name "unconnected-(U2-SDO-Pad5)") (class "Default")
      (node (ref "U2") (pin "5") (pinfunction "SDO_5") (pintype "bidirectional"))
    )
    (net (code "57") (name "unconnected-(V1-STAT_DIS-Pad4)") (class "Default")
      (node (ref "V1") (pin "4") (pinfunction "STAT_DIS_4") (pintype "passive"))
    )
    (net (code "58") (name "unconnected-(V2-STAT_DIS-Pad4)") (class "Default")
      (node (ref "V2") (pin "4") (pinfunction "STAT_DIS_4") (pintype "passive"))
    )
    (net (code "59") (name "unconnected-(V3-STAT_DIS-Pad4)") (class "Default")
      (node (ref "V3") (pin "4") (pinfunction "STAT_DIS_4") (pintype "passive"))
    )
    (net (code "60") (name "unconnected-(V4-STAT_DIS-Pad4)") (class "Default")
      (node (ref "V4") (pin "4") (pinfunction "STAT_DIS_4") (pintype "passive"))
    )
    (net (code "61") (name "unconnected-(V5-STAT_DIS-Pad4)") (class "Default")
      (node (ref "V5") (pin "4") (pinfunction "STAT_DIS_4") (pintype "passive"))
    )
    (net (code "62") (name "unconnected-(V6-STAT_DIS-Pad4)") (class "Default")
      (node (ref "V6") (pin "4") (pinfunction "STAT_DIS_4") (pintype "passive"))
    )
  )
)
